# NE555DXZD.net
KiCad netlist of a schematic drawn in Altium Designer
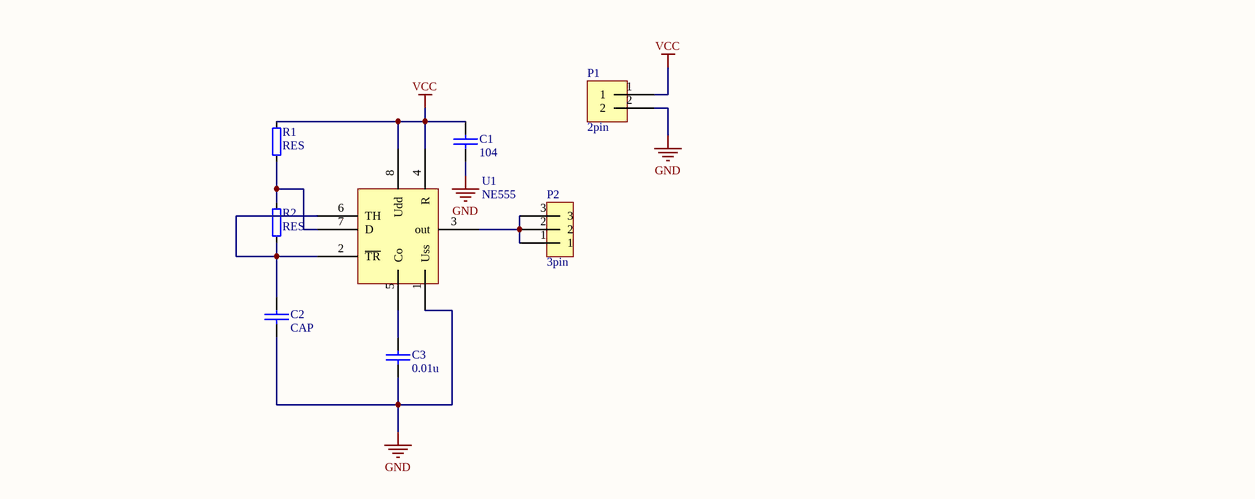
[diagram p0: NE555DXZD.SchDoc]

(export (version "E")
  (design (tool "Eeschema 10.0.6"))
  (components
    (comp (ref "C1") (value "104") (footprint "RAD0.1") (libsource (lib "fish") (part "CAP")))
    (comp (ref "C2") (value "CAP") (footprint "RAD0.1") (libsource (lib "fish") (part "CAP")))
    (comp (ref "C3") (value "0.01u") (footprint "RAD0.1") (libsource (lib "fish") (part "CAP")))
    (comp (ref "P1") (value "2pin") (footprint "2pin针") (libsource (lib "fish") (part "2pin")))
    (comp (ref "P2") (value "3pin") (footprint "3PIN排针") (libsource (lib "fish") (part "3pin")))
    (comp (ref "R1") (value "RES") (footprint "AXIAL0.4") (libsource (lib "fish") (part "RES")))
    (comp (ref "R2") (value "RES") (footprint "AXIAL0.4") (libsource (lib "fish") (part "RES")))
    (comp (ref "U1") (value "NE555") (footprint "8pin座") (libsource (lib "fish") (part "NE555")))
  )
  (nets
    (net (code "1") (name "GND") (class "Default")
      (node (ref "C1") (pin "2") (pinfunction "2_2") (pintype "passive"))
      (node (ref "C2") (pin "2") (pinfunction "2_2") (pintype "passive"))
      (node (ref "C3") (pin "2") (pinfunction "2_2") (pintype "passive"))
      (node (ref "P1") (pin "2") (pinfunction "2_2") (pintype "passive"))
      (node (ref "U1") (pin "1") (pinfunction "Uss_1") (pintype "passive"))
    )
    (net (code "2") (name "Net-(U1-Co)") (class "Default")
      (node (ref "C3") (pin "1") (pinfunction "1_1") (pintype "passive"))
      (node (ref "U1") (pin "5") (pinfunction "Co_5") (pintype "passive"))
    )
    (net (code "3") (name "Net-(U1-D)") (class "Default")
      (node (ref "R1") (pin "1") (pinfunction "1_1") (pintype "passive"))
      (node (ref "R2") (pin "2") (pinfunction "2_2") (pintype "passive"))
      (node (ref "U1") (pin "7") (pinfunction "D_7") (pintype "passive"))
    )
    (net (code "4") (name "Net-(U1-TH)") (class "Default")
      (node (ref "C2") (pin "1") (pinfunction "1_1") (pintype "passive"))
      (node (ref "R2") (pin "1") (pinfunction "1_1") (pintype "passive"))
      (node (ref "U1") (pin "2") (pinfunction "~{TR}_2") (pintype "passive"))
      (node (ref "U1") (pin "6") (pinfunction "TH_6") (pintype "passive"))
    )
    (net (code "5") (name "Net-(U1-out)") (class "Default")
      (node (ref "P2") (pin "1") (pinfunction "1_1") (pintype "passive"))
      (node (ref "P2") (pin "2") (pinfunction "2_2") (pintype "passive"))
      (node (ref "P2") (pin "3") (pinfunction "3_3") (pintype "passive"))
      (node (ref "U1") (pin "3") (pinfunction "out_3") (pintype "passive"))
    )
    (net (code "6") (name "VCC") (class "Default")
      (node (ref "C1") (pin "1") (pinfunction "1_1") (pintype "passive"))
      (node (ref "P1") (pin "1") (pinfunction "1_1") (pintype "passive"))
      (node (ref "R1") (pin "2") (pinfunction "2_2") (pintype "passive"))
      (node (ref "U1") (pin "4") (pinfunction "R_4") (pintype "passive"))
      (node (ref "U1") (pin "8") (pinfunction "Udd_8") (pintype "passive"))
    )
  )
)
